# miwi.net
KiCad netlist of a schematic drawn in Altium Designer
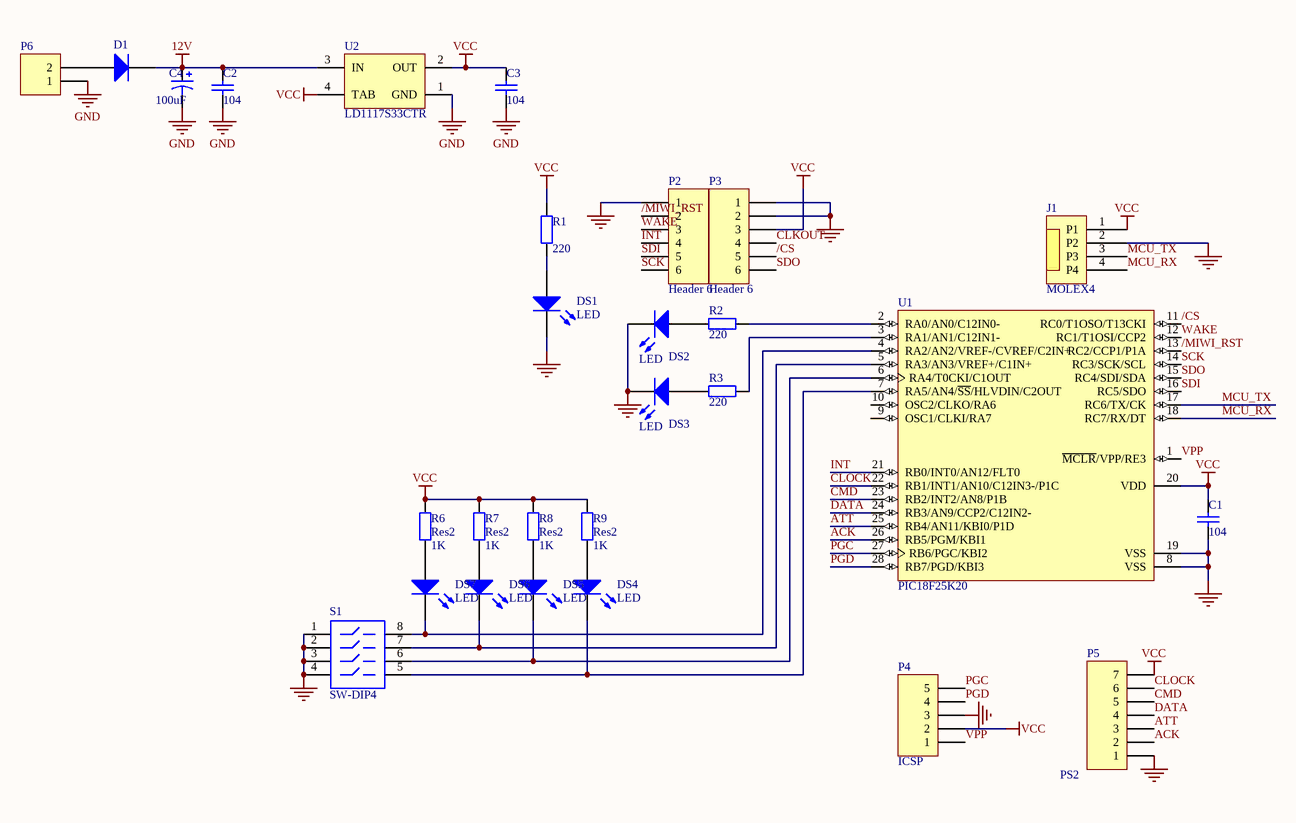
[diagram p0: miwi.SchDoc]

(export (version "E")
  (design (tool "Eeschema 10.0.6"))
  (components
    (comp (ref "C1")
      (value "104")
      (footprint "CAPR5.08-7.8x3.2")
      (description "Capacitor")
      (fields (field (name "PUBLISHER") "Altium Limited"))
      (libsource (lib "Miscellaneous Devices") (part "Cap"))
    )
    (comp (ref "C2")
      (value "104")
      (footprint "CAPR5.08-7.8x3.2")
      (description "Capacitor")
      (fields (field (name "PUBLISHER") "Altium Limited"))
      (libsource (lib "Miscellaneous Devices") (part "Cap"))
    )
    (comp (ref "C3")
      (value "104")
      (footprint "CAPR5.08-7.8x3.2")
      (description "Capacitor")
      (fields (field (name "PUBLISHER") "Altium Limited"))
      (libsource (lib "Miscellaneous Devices") (part "Cap"))
    )
    (comp (ref "C4")
      (value "100uF")
      (footprint "CAPPR2.5-6.3x5")
      (description "Polarized Capacitor (Radial)")
      (fields (field (name "PUBLISHER") "Altium Limited"))
      (libsource (lib "Miscellaneous Devices") (part "Cap Pol1"))
    )
    (comp (ref "D1")
      (value "MULTICOMP - S3J - DIODE, STANDARD, 3A, 600V, SMD")
      (footprint "SMC")
      (description "Default Diode")
      (fields (field (name "PUBLISHER") "Altium Limited"))
      (libsource (lib "Miscellaneous Devices") (part "Diode"))
    )
    (comp (ref "DS1") (value "LED") (footprint "LED") (libsource (lib "*") (part "LED")))
    (comp (ref "DS2") (value "LED") (footprint "LED") (libsource (lib "*") (part "LED")))
    (comp (ref "DS3") (value "LED") (footprint "LED") (libsource (lib "*") (part "LED")))
    (comp (ref "DS4") (value "LED") (footprint "LED") (libsource (lib "misc") (part "LED")))
    (comp (ref "DS5") (value "LED") (footprint "LED") (libsource (lib "misc") (part "LED")))
    (comp (ref "DS6") (value "LED") (footprint "LED") (libsource (lib "misc") (part "LED")))
    (comp (ref "DS7") (value "LED") (footprint "LED") (libsource (lib "misc") (part "LED")))
    (comp (ref "J1") (value "MOLEX4") (footprint "MOLEX4") (libsource (lib "molex") (part "MOLEX4")))
    (comp (ref "P2")
      (value "Header 6")
      (footprint "HDR1X6")
      (description "Header, 6-Pin")
      (fields (field (name "PUBLISHER") "Altium Limited"))
      (libsource (lib "") (part "Header 6_1"))
    )
    (comp (ref "P3")
      (value "Header 6")
      (footprint "HDR1X6")
      (description "Header, 6-Pin")
      (fields (field (name "PUBLISHER") "Altium Limited"))
      (libsource (lib "Miscellaneous Connectors") (part "Header 6"))
    )
    (comp (ref "P4")
      (value "ICSP")
      (footprint "HDR1X5")
      (description "Header, 5-Pin")
      (fields (field (name "PUBLISHER") "Altium Limited"))
      (libsource (lib "Miscellaneous Connectors") (part "Header 5"))
    )
    (comp (ref "P5")
      (value "PS2")
      (footprint "KK Header 6410-7")
      (description "Header, 7-Pin, KK Header 6410, 100mil")
      (fields (field (name "PUBLISHER") "Altium Limited"))
      (libsource (lib "varslib") (part "Header 7 Type 1"))
    )
    (comp (ref "P6")
      (value "12V Input")
      (footprint "KK Header 6410-2")
      (description "Header, 2-Pin, KK Header 6410, 100mil")
      (fields (field (name "PUBLISHER") "Altium Limited"))
      (libsource (lib "varslib") (part "Header 2 Type 1"))
    )
    (comp (ref "R1")
      (value "220")
      (footprint "AXIAL-0.4")
      (description "Resistor")
      (fields (field (name "PUBLISHER") "Altium Limited"))
      (libsource (lib "Miscellaneous Devices") (part "Res2"))
    )
    (comp (ref "R2")
      (value "220")
      (footprint "AXIAL-0.4")
      (description "Resistor")
      (fields (field (name "PUBLISHER") "Altium Limited"))
      (libsource (lib "") (part "Res2_1"))
    )
    (comp (ref "R3")
      (value "220")
      (footprint "AXIAL-0.4")
      (description "Resistor")
      (fields (field (name "PUBLISHER") "Altium Limited"))
      (libsource (lib "") (part "Res2_1"))
    )
    (comp (ref "R6")
      (value "Res2")
      (footprint "AXIAL-0.4")
      (description "Resistor")
      (fields (field (name "ALTIUM_VALUE") "1K") (field (name "PUBLISHER") "Altium Limited"))
      (libsource (lib "Miscellaneous Devices") (part "Res2"))
    )
    (comp (ref "R7")
      (value "Res2")
      (footprint "AXIAL-0.4")
      (description "Resistor")
      (fields (field (name "ALTIUM_VALUE") "1K") (field (name "PUBLISHER") "Altium Limited"))
      (libsource (lib "Miscellaneous Devices") (part "Res2"))
    )
    (comp (ref "R8")
      (value "Res2")
      (footprint "AXIAL-0.4")
      (description "Resistor")
      (fields (field (name "ALTIUM_VALUE") "1K") (field (name "PUBLISHER") "Altium Limited"))
      (libsource (lib "Miscellaneous Devices") (part "Res2"))
    )
    (comp (ref "R9")
      (value "Res2")
      (footprint "AXIAL-0.4")
      (description "Resistor")
      (fields (field (name "ALTIUM_VALUE") "1K") (field (name "PUBLISHER") "Altium Limited"))
      (libsource (lib "Miscellaneous Devices") (part "Res2"))
    )
    (comp (ref "S1")
      (value "SW-DIP4")
      (footprint "DIP-8")
      (description "DIP Switch")
      (fields (field (name "PUBLISHER") "Altium Limited"))
      (libsource (lib "Miscellaneous Devices") (part "SW-DIP4"))
    )
    (comp (ref "U1") (value "PIC18F25K20") (footprint "PDIP-28") (libsource (lib "*") (part "PIC18F25K20")))
    (comp (ref "U2")
      (value "LD1117S33CTR")
      (footprint "MP04A_N")
      (description "800mA Low-Dropout Linear Regulator, 4-pin SOT-223")
      (fields
        (field (name "PARTNUMBER") "LM1117IMPX-3.3")
        (field (name "MANUFACTURER") "National Semiconductor")
        (field (name "PUBLISHER") "Altium Limited")
      )
      (libsource (lib "NSC LDO") (part "LM1117IMPX-3.3"))
    )
  )
  (nets
    (net (code "1") (name "/ACK") (class "Default")
      (node (ref "P5") (pin "2") (pinfunction "2_2") (pintype "passive"))
      (node (ref "U1") (pin "26") (pinfunction "RB5/PGM/KBI1_26") (pintype "bidirectional"))
    )
    (net (code "2") (name "/ATT") (class "Default")
      (node (ref "P5") (pin "3") (pinfunction "3_3") (pintype "passive"))
      (node (ref "U1") (pin "25") (pinfunction "RB4/AN11/KBI0/P1D_25") (pintype "bidirectional"))
    )
    (net (code "3") (name "/CLKOUT") (class "Default")
      (node (ref "P3") (pin "4") (pinfunction "4_4") (pintype "passive"))
    )
    (net (code "4") (name "/CLOCK") (class "Default")
      (node (ref "P5") (pin "6") (pinfunction "6_6") (pintype "passive"))
      (node (ref "U1") (pin "22") (pinfunction "RB1/INT1/AN10/C12IN3-/P1C_22") (pintype "bidirectional"))
    )
    (net (code "5") (name "/CMD") (class "Default")
      (node (ref "P5") (pin "5") (pinfunction "5_5") (pintype "passive"))
      (node (ref "U1") (pin "23") (pinfunction "RB2/INT2/AN8/P1B_23") (pintype "bidirectional"))
    )
    (net (code "6") (name "/DATA") (class "Default")
      (node (ref "P5") (pin "4") (pinfunction "4_4") (pintype "passive"))
      (node (ref "U1") (pin "24") (pinfunction "RB3/AN9/CCP2/C12IN2-_24") (pintype "bidirectional"))
    )
    (net (code "7") (name "/INT") (class "Default")
      (node (ref "P2") (pin "4") (pinfunction "4_4") (pintype "passive"))
      (node (ref "U1") (pin "21") (pinfunction "RB0/INT0/AN12/FLT0_21") (pintype "bidirectional"))
    )
    (net (code "8") (name "/MCU_RX") (class "Default")
      (node (ref "J1") (pin "4") (pinfunction "P4_4") (pintype "passive"))
      (node (ref "U1") (pin "18") (pinfunction "RC7/RX/DT_18") (pintype "bidirectional"))
    )
    (net (code "9") (name "/MCU_TX") (class "Default")
      (node (ref "J1") (pin "3") (pinfunction "P3_3") (pintype "passive"))
      (node (ref "U1") (pin "17") (pinfunction "RC6/TX/CK_17") (pintype "bidirectional"))
    )
    (net (code "10") (name "/PGC") (class "Default")
      (node (ref "P4") (pin "5") (pinfunction "5_5") (pintype "passive"))
      (node (ref "U1") (pin "27") (pinfunction "RB6/PGC/KBI2_27") (pintype "bidirectional"))
    )
    (net (code "11") (name "/PGD") (class "Default")
      (node (ref "P4") (pin "4") (pinfunction "4_4") (pintype "passive"))
      (node (ref "U1") (pin "28") (pinfunction "RB7/PGD/KBI3_28") (pintype "bidirectional"))
    )
    (net (code "12") (name "/SCK") (class "Default")
      (node (ref "P2") (pin "6") (pinfunction "6_6") (pintype "passive"))
      (node (ref "U1") (pin "14") (pinfunction "RC3/SCK/SCL_14") (pintype "bidirectional"))
    )
    (net (code "13") (name "/SDI") (class "Default")
      (node (ref "P2") (pin "5") (pinfunction "5_5") (pintype "passive"))
      (node (ref "U1") (pin "16") (pinfunction "RC5/SDO_16") (pintype "bidirectional"))
    )
    (net (code "14") (name "/SDO") (class "Default")
      (node (ref "P3") (pin "6") (pinfunction "6_6") (pintype "passive"))
      (node (ref "U1") (pin "15") (pinfunction "RC4/SDI/SDA_15") (pintype "bidirectional"))
    )
    (net (code "15") (name "/VPP") (class "Default")
      (node (ref "P4") (pin "1") (pinfunction "1_1") (pintype "passive"))
      (node (ref "U1") (pin "1") (pinfunction "~{MCLR}/VPP/RE3_1") (pintype "bidirectional"))
    )
    (net (code "16") (name "/WAKE") (class "Default")
      (node (ref "P2") (pin "3") (pinfunction "3_3") (pintype "passive"))
      (node (ref "U1") (pin "12") (pinfunction "RC1/T1OSI/CCP2_12") (pintype "bidirectional"))
    )
    (net (code "17") (name "/{slash}CS") (class "Default")
      (node (ref "P3") (pin "5") (pinfunction "5_5") (pintype "passive"))
      (node (ref "U1") (pin "11") (pinfunction "RC0/T1OSO/T13CKI_11") (pintype "bidirectional"))
    )
    (net (code "18") (name "/{slash}MIWI_RST") (class "Default")
      (node (ref "P2") (pin "2") (pinfunction "2_2") (pintype "passive"))
      (node (ref "U1") (pin "13") (pinfunction "RC2/CCP1/P1A_13") (pintype "bidirectional"))
    )
    (net (code "19") (name "12V") (class "Default")
      (node (ref "C2") (pin "2") (pinfunction "2_2") (pintype "passive"))
      (node (ref "C4") (pin "1") (pinfunction "1_1") (pintype "passive"))
      (node (ref "D1") (pin "2") (pinfunction "K_2") (pintype "passive"))
      (node (ref "U2") (pin "3") (pinfunction "IN_3") (pintype "power_in"))
    )
    (net (code "20") (name "GND") (class "Default")
      (node (ref "C1") (pin "1") (pinfunction "1_1") (pintype "passive"))
      (node (ref "C2") (pin "1") (pinfunction "1_1") (pintype "passive"))
      (node (ref "C3") (pin "1") (pinfunction "1_1") (pintype "passive"))
      (node (ref "C4") (pin "2") (pinfunction "2_2") (pintype "passive"))
      (node (ref "DS1") (pin "2") (pinfunction "K_2") (pintype "passive"))
      (node (ref "DS2") (pin "2") (pinfunction "K_2") (pintype "passive"))
      (node (ref "DS3") (pin "2") (pinfunction "K_2") (pintype "passive"))
      (node (ref "J1") (pin "2") (pinfunction "P2_2") (pintype "passive"))
      (node (ref "P2") (pin "1") (pinfunction "1_1") (pintype "passive"))
      (node (ref "P3") (pin "1") (pinfunction "1_1") (pintype "passive"))
      (node (ref "P3") (pin "2") (pinfunction "2_2") (pintype "passive"))
      (node (ref "P4") (pin "3") (pinfunction "3_3") (pintype "passive"))
      (node (ref "P5") (pin "1") (pinfunction "1_1") (pintype "passive"))
      (node (ref "P6") (pin "1") (pinfunction "1_1") (pintype "passive"))
      (node (ref "S1") (pin "1") (pinfunction "1_1") (pintype "passive"))
      (node (ref "S1") (pin "2") (pinfunction "2_2") (pintype "passive"))
      (node (ref "S1") (pin "3") (pinfunction "3_3") (pintype "passive"))
      (node (ref "S1") (pin "4") (pinfunction "4_4") (pintype "passive"))
      (node (ref "U1") (pin "19") (pinfunction "VSS_19") (pintype "power_in"))
      (node (ref "U1") (pin "8") (pinfunction "VSS_8") (pintype "power_in"))
      (node (ref "U2") (pin "1") (pinfunction "GND_1") (pintype "power_in"))
    )
    (net (code "21") (name "Net-(D1-A)") (class "Default")
      (node (ref "D1") (pin "1") (pinfunction "A_1") (pintype "passive"))
      (node (ref "P6") (pin "2") (pinfunction "2_2") (pintype "passive"))
    )
    (net (code "22") (name "Net-(DS1-A)") (class "Default")
      (node (ref "DS1") (pin "1") (pinfunction "A_1") (pintype "passive"))
      (node (ref "R1") (pin "1") (pinfunction "1_1") (pintype "passive"))
    )
    (net (code "23") (name "Net-(DS2-A)") (class "Default")
      (node (ref "DS2") (pin "1") (pinfunction "A_1") (pintype "passive"))
      (node (ref "R2") (pin "1") (pinfunction "1_1") (pintype "passive"))
    )
    (net (code "24") (name "Net-(DS3-A)") (class "Default")
      (node (ref "DS3") (pin "1") (pinfunction "A_1") (pintype "passive"))
      (node (ref "R3") (pin "1") (pinfunction "1_1") (pintype "passive"))
    )
    (net (code "25") (name "Net-(DS4-A)") (class "Default")
      (node (ref "DS4") (pin "1") (pinfunction "A_1") (pintype "passive"))
      (node (ref "R9") (pin "1") (pinfunction "1_1") (pintype "passive"))
    )
    (net (code "26") (name "Net-(DS4-K)") (class "Default")
      (node (ref "DS4") (pin "2") (pinfunction "K_2") (pintype "passive"))
      (node (ref "S1") (pin "5") (pinfunction "5_5") (pintype "passive"))
      (node (ref "U1") (pin "7") (pinfunction "RA5/AN4/~{SS}/HLVDIN/C2OUT_7") (pintype "bidirectional"))
    )
    (net (code "27") (name "Net-(DS5-A)") (class "Default")
      (node (ref "DS5") (pin "1") (pinfunction "A_1") (pintype "passive"))
      (node (ref "R8") (pin "1") (pinfunction "1_1") (pintype "passive"))
    )
    (net (code "28") (name "Net-(DS5-K)") (class "Default")
      (node (ref "DS5") (pin "2") (pinfunction "K_2") (pintype "passive"))
      (node (ref "S1") (pin "6") (pinfunction "6_6") (pintype "passive"))
      (node (ref "U1") (pin "6") (pinfunction "RA4/T0CKI/C1OUT_6") (pintype "bidirectional"))
    )
    (net (code "29") (name "Net-(DS6-A)") (class "Default")
      (node (ref "DS6") (pin "1") (pinfunction "A_1") (pintype "passive"))
      (node (ref "R7") (pin "1") (pinfunction "1_1") (pintype "passive"))
    )
    (net (code "30") (name "Net-(DS6-K)") (class "Default")
      (node (ref "DS6") (pin "2") (pinfunction "K_2") (pintype "passive"))
      (node (ref "S1") (pin "7") (pinfunction "7_7") (pintype "passive"))
      (node (ref "U1") (pin "5") (pinfunction "RA3/AN3/VREF+/C1IN+_5") (pintype "bidirectional"))
    )
    (net (code "31") (name "Net-(DS7-A)") (class "Default")
      (node (ref "DS7") (pin "1") (pinfunction "A_1") (pintype "passive"))
      (node (ref "R6") (pin "1") (pinfunction "1_1") (pintype "passive"))
    )
    (net (code "32") (name "Net-(DS7-K)") (class "Default")
      (node (ref "DS7") (pin "2") (pinfunction "K_2") (pintype "passive"))
      (node (ref "S1") (pin "8") (pinfunction "8_8") (pintype "passive"))
      (node (ref "U1") (pin "4") (pinfunction "RA2/AN2/VREF-/CVREF/C2IN+_4") (pintype "bidirectional"))
    )
    (net (code "33") (name "Net-(U1-RA0{slash}AN0{slash}C12IN0-)") (class "Default")
      (node (ref "R2") (pin "2") (pinfunction "2_2") (pintype "passive"))
      (node (ref "U1") (pin "2") (pinfunction "RA0/AN0/C12IN0-_2") (pintype "bidirectional"))
    )
    (net (code "34") (name "Net-(U1-RA1{slash}AN1{slash}C12IN1-)") (class "Default")
      (node (ref "R3") (pin "2") (pinfunction "2_2") (pintype "passive"))
      (node (ref "U1") (pin "3") (pinfunction "RA1/AN1/C12IN1-_3") (pintype "bidirectional"))
    )
    (net (code "35") (name "VCC") (class "Default")
      (node (ref "C1") (pin "2") (pinfunction "2_2") (pintype "passive"))
      (node (ref "C3") (pin "2") (pinfunction "2_2") (pintype "passive"))
      (node (ref "J1") (pin "1") (pinfunction "P1_1") (pintype "passive"))
      (node (ref "P3") (pin "3") (pinfunction "3_3") (pintype "passive"))
      (node (ref "P4") (pin "2") (pinfunction "2_2") (pintype "passive"))
      (node (ref "P5") (pin "7") (pinfunction "7_7") (pintype "passive"))
      (node (ref "R1") (pin "2") (pinfunction "2_2") (pintype "passive"))
      (node (ref "R6") (pin "2") (pinfunction "2_2") (pintype "passive"))
      (node (ref "R7") (pin "2") (pinfunction "2_2") (pintype "passive"))
      (node (ref "R8") (pin "2") (pinfunction "2_2") (pintype "passive"))
      (node (ref "R9") (pin "2") (pinfunction "2_2") (pintype "passive"))
      (node (ref "U1") (pin "20") (pinfunction "VDD_20") (pintype "power_in"))
      (node (ref "U2") (pin "2") (pinfunction "OUT_2") (pintype "power_in"))
      (node (ref "U2") (pin "4") (pinfunction "TAB_4") (pintype "power_in"))
    )
    (net (code "36") (name "unconnected-(U1-OSC1{slash}CLKI{slash}RA7-Pad9)") (class "Default")
      (node (ref "U1") (pin "9") (pinfunction "OSC1/CLKI/RA7_9") (pintype "bidirectional"))
    )
    (net (code "37") (name "unconnected-(U1-OSC2{slash}CLKO{slash}RA6-Pad10)") (class "Default")
      (node (ref "U1") (pin "10") (pinfunction "OSC2/CLKO/RA6_10") (pintype "bidirectional"))
    )
  )
)
